# FishingReelController.net
KiCad netlist of a schematic drawn in EAGLE
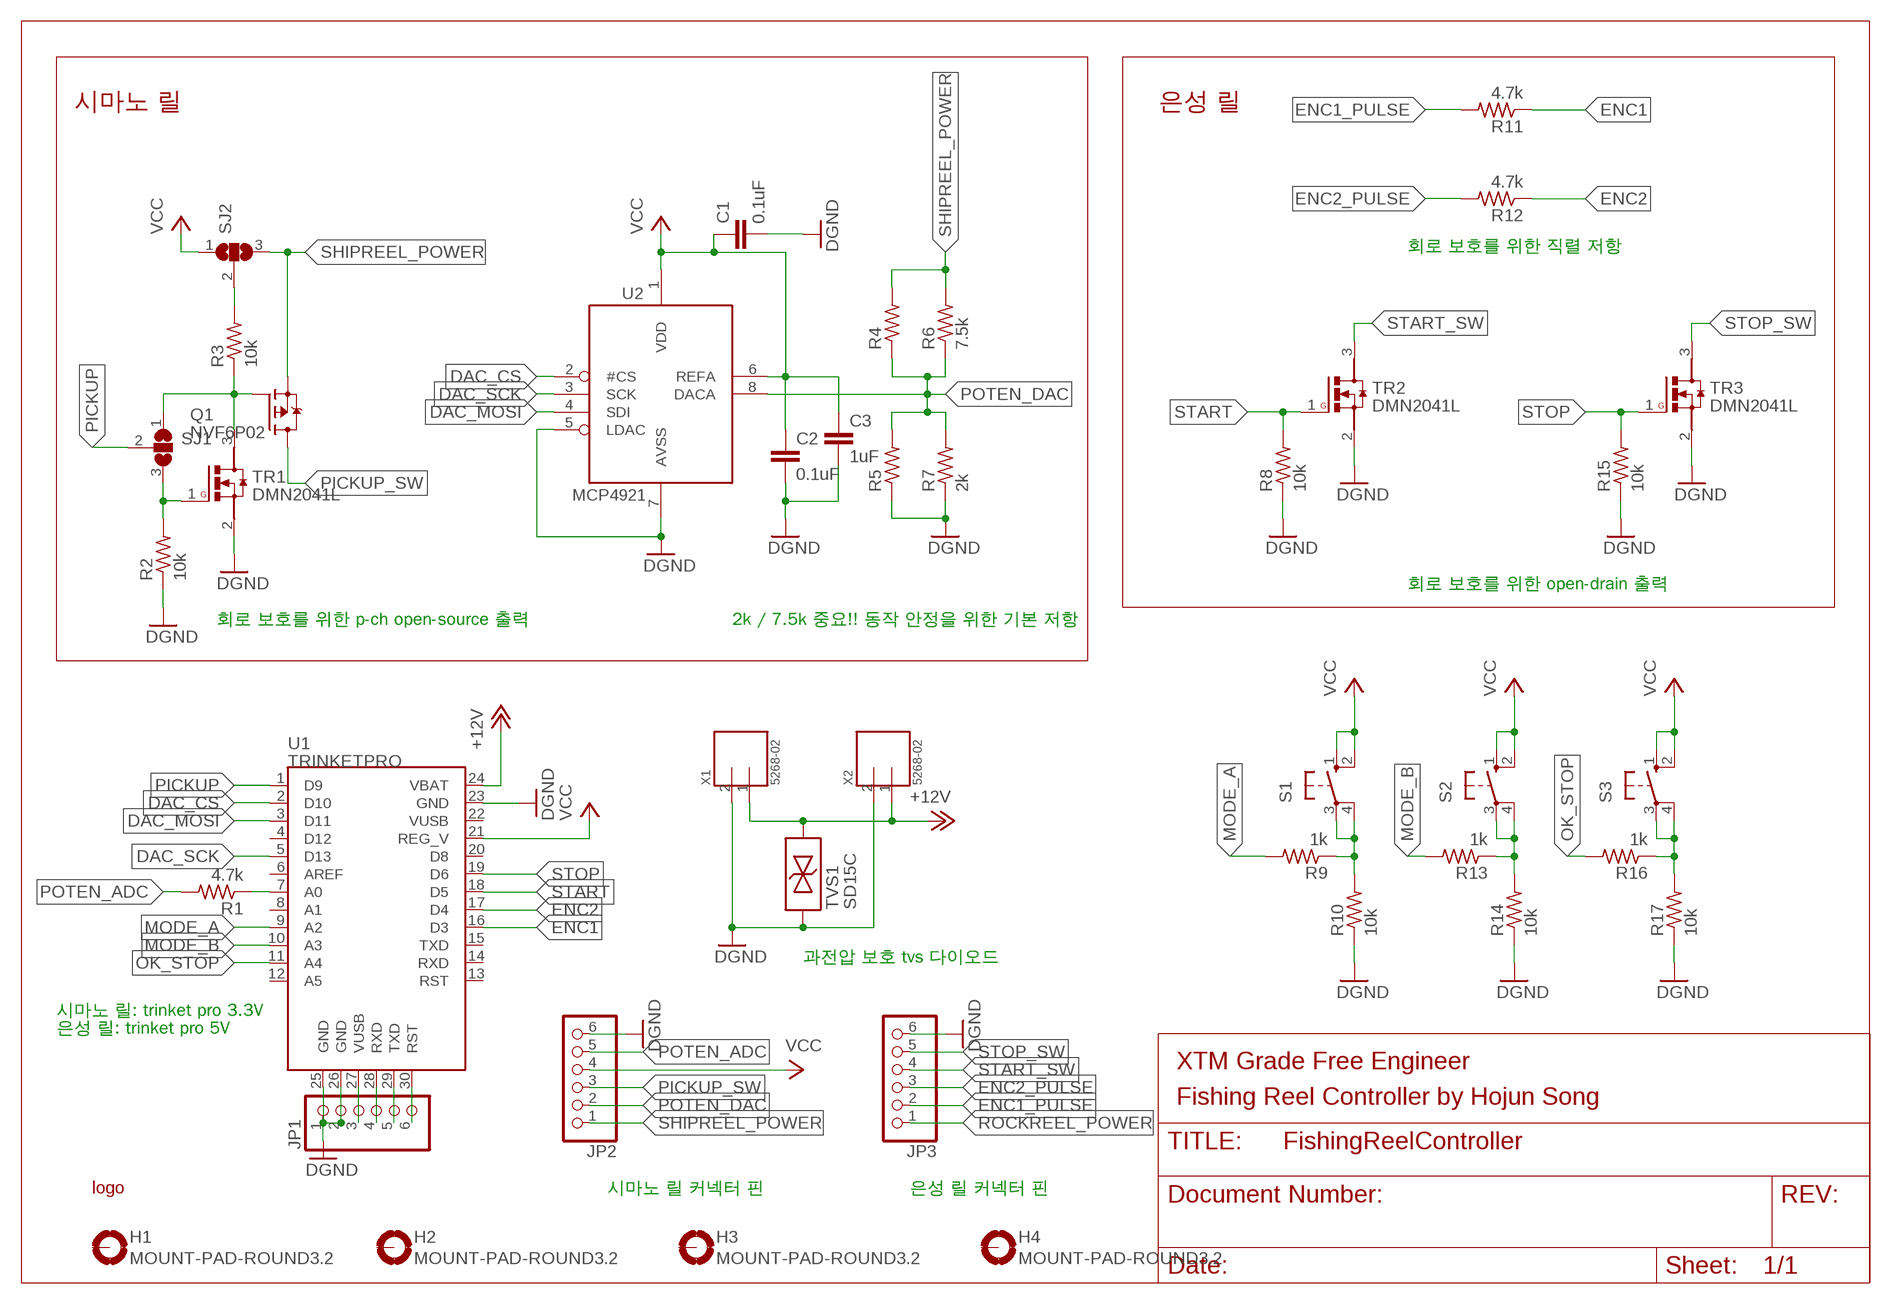
[diagram p0: schematic, sheet 1]

(export (version "E")
  (design (tool "Eeschema 10.0.6"))
  (components
    (comp (ref "C1")
      (value "0.1uF")
      (footprint "eagle-import:C0603(1608)")
      (libsource (lib "eagle-import") (part "C0603(1608)"))
    )
    (comp (ref "C2")
      (value "0.1uF")
      (footprint "eagle-import:C0603(1608)")
      (libsource (lib "eagle-import") (part "C0603(1608)"))
    )
    (comp (ref "C3")
      (value "1uF")
      (footprint "eagle-import:C0603(1608)")
      (libsource (lib "eagle-import") (part "C0603(1608)"))
    )
    (comp (ref "H1")
      (value "MOUNT-PAD-ROUND3.2")
      (footprint "eagle-import:3,2-PAD")
      (libsource (lib "eagle-import") (part "MOUNT-PAD-ROUND3.2"))
    )
    (comp (ref "H2")
      (value "MOUNT-PAD-ROUND3.2")
      (footprint "eagle-import:3,2-PAD")
      (libsource (lib "eagle-import") (part "MOUNT-PAD-ROUND3.2"))
    )
    (comp (ref "H3")
      (value "MOUNT-PAD-ROUND3.2")
      (footprint "eagle-import:3,2-PAD")
      (libsource (lib "eagle-import") (part "MOUNT-PAD-ROUND3.2"))
    )
    (comp (ref "H4")
      (value "MOUNT-PAD-ROUND3.2")
      (footprint "eagle-import:3,2-PAD")
      (libsource (lib "eagle-import") (part "MOUNT-PAD-ROUND3.2"))
    )
    (comp (ref "JP1")
      (value "PINHD-1X6CB")
      (footprint "eagle-import:1X06-CLEANBIG")
      (libsource (lib "eagle-import") (part "PINHD-1X6CB"))
    )
    (comp (ref "JP2")
      (value "PINHD-1X6CB")
      (footprint "eagle-import:1X06-CLEANBIG")
      (libsource (lib "eagle-import") (part "PINHD-1X6CB"))
    )
    (comp (ref "JP3")
      (value "PINHD-1X6CB")
      (footprint "eagle-import:1X06-CLEANBIG")
      (libsource (lib "eagle-import") (part "PINHD-1X6CB"))
    )
    (comp (ref "LOGO1")
      (value "GRADEFREELOGO-20")
      (footprint "eagle-import:GRADEFREELOGO-20")
      (libsource (lib "eagle-import") (part "GRADEFREELOGO-20"))
    )
    (comp (ref "Q1")
      (value "NVF6P02")
      (footprint "eagle-import:SOT223")
      (libsource (lib "eagle-import") (part "NVF6P02"))
    )
    (comp (ref "R1")
      (value "4.7k")
      (footprint "eagle-import:R0603(1608)")
      (libsource (lib "eagle-import") (part "R0603(1608)"))
    )
    (comp (ref "R2")
      (value "10k")
      (footprint "eagle-import:R0603(1608)")
      (libsource (lib "eagle-import") (part "R0603(1608)"))
    )
    (comp (ref "R3")
      (value "10k")
      (footprint "eagle-import:R0603(1608)")
      (libsource (lib "eagle-import") (part "R0603(1608)"))
    )
    (comp (ref "R4")
      (value "R0603(1608)")
      (footprint "eagle-import:R0603(1608)")
      (libsource (lib "eagle-import") (part "R0603(1608)"))
    )
    (comp (ref "R5")
      (value "R0603(1608)")
      (footprint "eagle-import:R0603(1608)")
      (libsource (lib "eagle-import") (part "R0603(1608)"))
    )
    (comp (ref "R6")
      (value "7.5k")
      (footprint "eagle-import:R0603(1608)")
      (libsource (lib "eagle-import") (part "R0603(1608)"))
    )
    (comp (ref "R7")
      (value "2k")
      (footprint "eagle-import:R0603(1608)")
      (libsource (lib "eagle-import") (part "R0603(1608)"))
    )
    (comp (ref "R8")
      (value "10k")
      (footprint "eagle-import:R0603(1608)")
      (libsource (lib "eagle-import") (part "R0603(1608)"))
    )
    (comp (ref "R9")
      (value "1k")
      (footprint "eagle-import:R0603(1608)")
      (libsource (lib "eagle-import") (part "R0603(1608)"))
    )
    (comp (ref "R10")
      (value "10k")
      (footprint "eagle-import:R0603(1608)")
      (libsource (lib "eagle-import") (part "R0603(1608)"))
    )
    (comp (ref "R11")
      (value "4.7k")
      (footprint "eagle-import:R0603(1608)")
      (libsource (lib "eagle-import") (part "R0603(1608)"))
    )
    (comp (ref "R12")
      (value "4.7k")
      (footprint "eagle-import:R0603(1608)")
      (libsource (lib "eagle-import") (part "R0603(1608)"))
    )
    (comp (ref "R13")
      (value "1k")
      (footprint "eagle-import:R0603(1608)")
      (libsource (lib "eagle-import") (part "R0603(1608)"))
    )
    (comp (ref "R14")
      (value "10k")
      (footprint "eagle-import:R0603(1608)")
      (libsource (lib "eagle-import") (part "R0603(1608)"))
    )
    (comp (ref "R15")
      (value "10k")
      (footprint "eagle-import:R0603(1608)")
      (libsource (lib "eagle-import") (part "R0603(1608)"))
    )
    (comp (ref "R16")
      (value "1k")
      (footprint "eagle-import:R0603(1608)")
      (libsource (lib "eagle-import") (part "R0603(1608)"))
    )
    (comp (ref "R17")
      (value "10k")
      (footprint "eagle-import:R0603(1608)")
      (libsource (lib "eagle-import") (part "R0603(1608)"))
    )
    (comp (ref "S1")
      (value "40-XX")
      (footprint "eagle-import:B3F-40XX")
      (fields (field (name "MF") "OMRON COMPONENTS USA") (field (name "MPN") "B3F-4000"))
      (libsource (lib "eagle-import") (part "40-XX"))
    )
    (comp (ref "S2")
      (value "40-XX")
      (footprint "eagle-import:B3F-40XX")
      (fields (field (name "MF") "OMRON COMPONENTS USA") (field (name "MPN") "B3F-4000"))
      (libsource (lib "eagle-import") (part "40-XX"))
    )
    (comp (ref "S3")
      (value "40-XX")
      (footprint "eagle-import:B3F-40XX")
      (fields (field (name "MF") "OMRON COMPONENTS USA") (field (name "MPN") "B3F-4000"))
      (libsource (lib "eagle-import") (part "40-XX"))
    )
    (comp (ref "SJ1")
      (value "SJ2W")
      (footprint "eagle-import:SJ_2")
      (libsource (lib "eagle-import") (part "SJ2W"))
    )
    (comp (ref "SJ2")
      (value "SJ2W")
      (footprint "eagle-import:SJ_2")
      (libsource (lib "eagle-import") (part "SJ2W"))
    )
    (comp (ref "TR1")
      (value "DMN2041L")
      (footprint "eagle-import:SOT23")
      (libsource (lib "eagle-import") (part "DMN2041L"))
    )
    (comp (ref "TR2")
      (value "DMN2041L")
      (footprint "eagle-import:SOT23")
      (libsource (lib "eagle-import") (part "DMN2041L"))
    )
    (comp (ref "TR3")
      (value "DMN2041L")
      (footprint "eagle-import:SOT23")
      (libsource (lib "eagle-import") (part "DMN2041L"))
    )
    (comp (ref "TVS1")
      (value "SD15C")
      (footprint "eagle-import:SOD-323-NOPOL")
      (libsource (lib "eagle-import") (part "SD0"))
    )
    (comp (ref "U1")
      (value "TRINKETPRO")
      (footprint "eagle-import:TRINKETPRO")
      (libsource (lib "eagle-import") (part "TRINKETPRO"))
    )
    (comp (ref "U2")
      (value "MCP4921")
      (footprint "eagle-import:DIL08")
      (libsource (lib "eagle-import") (part "MCP4921"))
    )
    (comp (ref "X1")
      (value "5268-02")
      (footprint "eagle-import:5628-02")
      (libsource (lib "eagle-import") (part "5268-02"))
    )
    (comp (ref "X2")
      (value "5268-02")
      (footprint "eagle-import:5628-02")
      (libsource (lib "eagle-import") (part "5268-02"))
    )
  )
  (nets
    (net (code "1") (name "+12V") (class "Default")
      (node (ref "TVS1") (pin "2") (pinfunction "P$2_2") (pintype "bidirectional"))
      (node (ref "U1") (pin "24") (pinfunction "VBAT_24") (pintype "bidirectional"))
      (node (ref "X1") (pin "1") (pinfunction "1_1") (pintype "bidirectional"))
      (node (ref "X2") (pin "1") (pinfunction "1_1") (pintype "bidirectional"))
    )
    (net (code "2") (name "DAC_CS") (class "Default")
      (node (ref "U1") (pin "2") (pinfunction "D10_2") (pintype "bidirectional"))
      (node (ref "U2") (pin "2") (pinfunction "#CS_2") (pintype "input"))
    )
    (net (code "3") (name "DAC_MOSI") (class "Default")
      (node (ref "U1") (pin "3") (pinfunction "D11_3") (pintype "bidirectional"))
      (node (ref "U2") (pin "4") (pinfunction "SDI_4") (pintype "input"))
    )
    (net (code "4") (name "DAC_SCK") (class "Default")
      (node (ref "U1") (pin "5") (pinfunction "D13_5") (pintype "bidirectional"))
      (node (ref "U2") (pin "3") (pinfunction "SCK_3") (pintype "input"))
    )
    (net (code "5") (name "DGND") (class "Default")
      (node (ref "C1") (pin "2") (pinfunction "2_2") (pintype "passive"))
      (node (ref "C2") (pin "2") (pinfunction "2_2") (pintype "passive"))
      (node (ref "C3") (pin "2") (pinfunction "2_2") (pintype "passive"))
      (node (ref "JP1") (pin "1") (pinfunction "1_1") (pintype "passive"))
      (node (ref "JP1") (pin "2") (pinfunction "2_2") (pintype "passive"))
      (node (ref "JP2") (pin "6") (pinfunction "6_6") (pintype "passive"))
      (node (ref "JP3") (pin "6") (pinfunction "6_6") (pintype "passive"))
      (node (ref "R10") (pin "1") (pinfunction "1_1") (pintype "passive"))
      (node (ref "R14") (pin "1") (pinfunction "1_1") (pintype "passive"))
      (node (ref "R15") (pin "1") (pinfunction "1_1") (pintype "passive"))
      (node (ref "R17") (pin "1") (pinfunction "1_1") (pintype "passive"))
      (node (ref "R2") (pin "1") (pinfunction "1_1") (pintype "passive"))
      (node (ref "R5") (pin "1") (pinfunction "1_1") (pintype "passive"))
      (node (ref "R7") (pin "1") (pinfunction "1_1") (pintype "passive"))
      (node (ref "R8") (pin "1") (pinfunction "1_1") (pintype "passive"))
      (node (ref "TR1") (pin "2") (pinfunction "S_2") (pintype "bidirectional"))
      (node (ref "TR2") (pin "2") (pinfunction "S_2") (pintype "bidirectional"))
      (node (ref "TR3") (pin "2") (pinfunction "S_2") (pintype "bidirectional"))
      (node (ref "TVS1") (pin "1") (pinfunction "P$1_1") (pintype "bidirectional"))
      (node (ref "U1") (pin "23") (pinfunction "GND_23") (pintype "bidirectional"))
      (node (ref "U1") (pin "25") (pinfunction "GND_25") (pintype "bidirectional"))
      (node (ref "U1") (pin "26") (pinfunction "GND_26") (pintype "bidirectional"))
      (node (ref "U2") (pin "5") (pinfunction "LDAC_5") (pintype "input"))
      (node (ref "U2") (pin "7") (pinfunction "AVSS_7") (pintype "power_in"))
      (node (ref "X1") (pin "2") (pinfunction "2_2") (pintype "bidirectional"))
      (node (ref "X2") (pin "2") (pinfunction "2_2") (pintype "bidirectional"))
    )
    (net (code "6") (name "ENC1") (class "Default")
      (node (ref "R11") (pin "1") (pinfunction "1_1") (pintype "passive"))
      (node (ref "U1") (pin "16") (pinfunction "D3_16") (pintype "bidirectional"))
    )
    (net (code "7") (name "ENC1_PULSE") (class "Default")
      (node (ref "JP3") (pin "2") (pinfunction "2_2") (pintype "passive"))
      (node (ref "R11") (pin "2") (pinfunction "2_2") (pintype "passive"))
    )
    (net (code "8") (name "ENC2") (class "Default")
      (node (ref "R12") (pin "1") (pinfunction "1_1") (pintype "passive"))
      (node (ref "U1") (pin "17") (pinfunction "D4_17") (pintype "bidirectional"))
    )
    (net (code "9") (name "ENC2_PULSE") (class "Default")
      (node (ref "JP3") (pin "3") (pinfunction "3_3") (pintype "passive"))
      (node (ref "R12") (pin "2") (pinfunction "2_2") (pintype "passive"))
    )
    (net (code "10") (name "MODE_A") (class "Default")
      (node (ref "R9") (pin "2") (pinfunction "2_2") (pintype "passive"))
      (node (ref "U1") (pin "9") (pinfunction "A2_9") (pintype "bidirectional"))
    )
    (net (code "11") (name "MODE_B") (class "Default")
      (node (ref "R13") (pin "2") (pinfunction "2_2") (pintype "passive"))
      (node (ref "U1") (pin "10") (pinfunction "A3_10") (pintype "bidirectional"))
    )
    (net (code "12") (name "Net-(JP1-Pad3)") (class "Default")
      (node (ref "JP1") (pin "3") (pinfunction "3_3") (pintype "passive"))
      (node (ref "U1") (pin "27") (pinfunction "VUSB_27") (pintype "bidirectional"))
    )
    (net (code "13") (name "Net-(JP1-Pad4)") (class "Default")
      (node (ref "JP1") (pin "4") (pinfunction "4_4") (pintype "passive"))
      (node (ref "U1") (pin "28") (pinfunction "RXD_28") (pintype "bidirectional"))
    )
    (net (code "14") (name "Net-(JP1-Pad5)") (class "Default")
      (node (ref "JP1") (pin "5") (pinfunction "5_5") (pintype "passive"))
      (node (ref "U1") (pin "29") (pinfunction "TXD_29") (pintype "bidirectional"))
    )
    (net (code "15") (name "Net-(JP1-Pad6)") (class "Default")
      (node (ref "JP1") (pin "6") (pinfunction "6_6") (pintype "passive"))
      (node (ref "U1") (pin "30") (pinfunction "RST_30") (pintype "bidirectional"))
    )
    (net (code "16") (name "Net-(Q1-G)") (class "Default")
      (node (ref "Q1") (pin "1") (pinfunction "G_1") (pintype "passive"))
      (node (ref "R3") (pin "1") (pinfunction "1_1") (pintype "passive"))
      (node (ref "SJ1") (pin "1") (pinfunction "1_1") (pintype "passive"))
      (node (ref "TR1") (pin "3") (pinfunction "D_3") (pintype "bidirectional"))
    )
    (net (code "17") (name "Net-(R3-Pad2)") (class "Default")
      (node (ref "R3") (pin "2") (pinfunction "2_2") (pintype "passive"))
      (node (ref "SJ2") (pin "2") (pinfunction "2_2") (pintype "passive"))
    )
    (net (code "18") (name "Net-(S1-P)") (class "Default")
      (node (ref "R10") (pin "2") (pinfunction "2_2") (pintype "passive"))
      (node (ref "R9") (pin "1") (pinfunction "1_1") (pintype "passive"))
      (node (ref "S1") (pin "3") (pinfunction "P_3") (pintype "passive"))
      (node (ref "S1") (pin "4") (pinfunction "P1_4") (pintype "passive"))
    )
    (net (code "19") (name "Net-(S2-P)") (class "Default")
      (node (ref "R13") (pin "1") (pinfunction "1_1") (pintype "passive"))
      (node (ref "R14") (pin "2") (pinfunction "2_2") (pintype "passive"))
      (node (ref "S2") (pin "3") (pinfunction "P_3") (pintype "passive"))
      (node (ref "S2") (pin "4") (pinfunction "P1_4") (pintype "passive"))
    )
    (net (code "20") (name "Net-(S3-P)") (class "Default")
      (node (ref "R16") (pin "1") (pinfunction "1_1") (pintype "passive"))
      (node (ref "R17") (pin "2") (pinfunction "2_2") (pintype "passive"))
      (node (ref "S3") (pin "3") (pinfunction "P_3") (pintype "passive"))
      (node (ref "S3") (pin "4") (pinfunction "P1_4") (pintype "passive"))
    )
    (net (code "21") (name "Net-(TR1-G)") (class "Default")
      (node (ref "R2") (pin "2") (pinfunction "2_2") (pintype "passive"))
      (node (ref "SJ1") (pin "3") (pinfunction "3_3") (pintype "passive"))
      (node (ref "TR1") (pin "1") (pinfunction "G_1") (pintype "bidirectional"))
    )
    (net (code "22") (name "Net-(U1-A0)") (class "Default")
      (node (ref "R1") (pin "1") (pinfunction "1_1") (pintype "passive"))
      (node (ref "U1") (pin "7") (pinfunction "A0_7") (pintype "bidirectional"))
    )
    (net (code "23") (name "OK_STOP") (class "Default")
      (node (ref "R16") (pin "2") (pinfunction "2_2") (pintype "passive"))
      (node (ref "U1") (pin "11") (pinfunction "A4_11") (pintype "bidirectional"))
    )
    (net (code "24") (name "PICKUP") (class "Default")
      (node (ref "SJ1") (pin "2") (pinfunction "2_2") (pintype "passive"))
      (node (ref "U1") (pin "1") (pinfunction "D9_1") (pintype "bidirectional"))
    )
    (net (code "25") (name "PICKUP_SW") (class "Default")
      (node (ref "JP2") (pin "3") (pinfunction "3_3") (pintype "passive"))
      (node (ref "Q1") (pin "2") (pinfunction "D_2") (pintype "passive"))
      (node (ref "Q1") (pin "4") (pinfunction "D_4") (pintype "passive"))
    )
    (net (code "26") (name "POTEN_ADC") (class "Default")
      (node (ref "JP2") (pin "5") (pinfunction "5_5") (pintype "passive"))
      (node (ref "R1") (pin "2") (pinfunction "2_2") (pintype "passive"))
    )
    (net (code "27") (name "POTEN_DAC") (class "Default")
      (node (ref "JP2") (pin "2") (pinfunction "2_2") (pintype "passive"))
      (node (ref "R4") (pin "1") (pinfunction "1_1") (pintype "passive"))
      (node (ref "R5") (pin "2") (pinfunction "2_2") (pintype "passive"))
      (node (ref "R6") (pin "1") (pinfunction "1_1") (pintype "passive"))
      (node (ref "R7") (pin "2") (pinfunction "2_2") (pintype "passive"))
      (node (ref "U2") (pin "8") (pinfunction "DACA_8") (pintype "output"))
    )
    (net (code "28") (name "ROCKREEL_POWER") (class "Default")
      (node (ref "JP3") (pin "1") (pinfunction "1_1") (pintype "passive"))
    )
    (net (code "29") (name "SHIPREEL_POWER") (class "Default")
      (node (ref "JP2") (pin "1") (pinfunction "1_1") (pintype "passive"))
      (node (ref "Q1") (pin "3") (pinfunction "S_3") (pintype "passive"))
      (node (ref "R4") (pin "2") (pinfunction "2_2") (pintype "passive"))
      (node (ref "R6") (pin "2") (pinfunction "2_2") (pintype "passive"))
      (node (ref "SJ2") (pin "3") (pinfunction "3_3") (pintype "passive"))
    )
    (net (code "30") (name "START") (class "Default")
      (node (ref "R8") (pin "2") (pinfunction "2_2") (pintype "passive"))
      (node (ref "TR2") (pin "1") (pinfunction "G_1") (pintype "bidirectional"))
      (node (ref "U1") (pin "18") (pinfunction "D5_18") (pintype "bidirectional"))
    )
    (net (code "31") (name "START_SW") (class "Default")
      (node (ref "JP3") (pin "4") (pinfunction "4_4") (pintype "passive"))
      (node (ref "TR2") (pin "3") (pinfunction "D_3") (pintype "bidirectional"))
    )
    (net (code "32") (name "STOP") (class "Default")
      (node (ref "R15") (pin "2") (pinfunction "2_2") (pintype "passive"))
      (node (ref "TR3") (pin "1") (pinfunction "G_1") (pintype "bidirectional"))
      (node (ref "U1") (pin "19") (pinfunction "D6_19") (pintype "bidirectional"))
    )
    (net (code "33") (name "STOP_SW") (class "Default")
      (node (ref "JP3") (pin "5") (pinfunction "5_5") (pintype "passive"))
      (node (ref "TR3") (pin "3") (pinfunction "D_3") (pintype "bidirectional"))
    )
    (net (code "34") (name "VCC") (class "Default")
      (node (ref "C1") (pin "1") (pinfunction "1_1") (pintype "passive"))
      (node (ref "C2") (pin "1") (pinfunction "1_1") (pintype "passive"))
      (node (ref "C3") (pin "1") (pinfunction "1_1") (pintype "passive"))
      (node (ref "JP2") (pin "4") (pinfunction "4_4") (pintype "passive"))
      (node (ref "S1") (pin "1") (pinfunction "S_1") (pintype "passive"))
      (node (ref "S1") (pin "2") (pinfunction "S1_2") (pintype "passive"))
      (node (ref "S2") (pin "1") (pinfunction "S_1") (pintype "passive"))
      (node (ref "S2") (pin "2") (pinfunction "S1_2") (pintype "passive"))
      (node (ref "S3") (pin "1") (pinfunction "S_1") (pintype "passive"))
      (node (ref "S3") (pin "2") (pinfunction "S1_2") (pintype "passive"))
      (node (ref "SJ2") (pin "1") (pinfunction "1_1") (pintype "passive"))
      (node (ref "U1") (pin "21") (pinfunction "REG_V_21") (pintype "bidirectional"))
      (node (ref "U2") (pin "1") (pinfunction "VDD_1") (pintype "power_in"))
      (node (ref "U2") (pin "6") (pinfunction "REFA_6") (pintype "input"))
    )
    (net (code "35") (name "unconnected-(H1-MOUNT-PadB3,2)") (class "Default")
      (node (ref "H1") (pin "B3,2") (pinfunction "MOUNT_B3,2") (pintype "passive"))
    )
    (net (code "36") (name "unconnected-(H2-MOUNT-PadB3,2)") (class "Default")
      (node (ref "H2") (pin "B3,2") (pinfunction "MOUNT_B3,2") (pintype "passive"))
    )
    (net (code "37") (name "unconnected-(H3-MOUNT-PadB3,2)") (class "Default")
      (node (ref "H3") (pin "B3,2") (pinfunction "MOUNT_B3,2") (pintype "passive"))
    )
    (net (code "38") (name "unconnected-(H4-MOUNT-PadB3,2)") (class "Default")
      (node (ref "H4") (pin "B3,2") (pinfunction "MOUNT_B3,2") (pintype "passive"))
    )
    (net (code "39") (name "unconnected-(U1-A1-Pad8)") (class "Default")
      (node (ref "U1") (pin "8") (pinfunction "A1_8") (pintype "bidirectional"))
    )
    (net (code "40") (name "unconnected-(U1-A5-Pad12)") (class "Default")
      (node (ref "U1") (pin "12") (pinfunction "A5_12") (pintype "bidirectional"))
    )
    (net (code "41") (name "unconnected-(U1-AREF-Pad6)") (class "Default")
      (node (ref "U1") (pin "6") (pinfunction "AREF_6") (pintype "bidirectional"))
    )
    (net (code "42") (name "unconnected-(U1-D8-Pad20)") (class "Default")
      (node (ref "U1") (pin "20") (pinfunction "D8_20") (pintype "bidirectional"))
    )
    (net (code "43") (name "unconnected-(U1-D12-Pad4)") (class "Default")
      (node (ref "U1") (pin "4") (pinfunction "D12_4") (pintype "bidirectional"))
    )
    (net (code "44") (name "unconnected-(U1-RST-Pad13)") (class "Default")
      (node (ref "U1") (pin "13") (pinfunction "RST_13") (pintype "bidirectional"))
    )
    (net (code "45") (name "unconnected-(U1-RXD-Pad14)") (class "Default")
      (node (ref "U1") (pin "14") (pinfunction "RXD_14") (pintype "bidirectional"))
    )
    (net (code "46") (name "unconnected-(U1-TXD-Pad15)") (class "Default")
      (node (ref "U1") (pin "15") (pinfunction "TXD_15") (pintype "bidirectional"))
    )
    (net (code "47") (name "unconnected-(U1-VUSB-Pad22)") (class "Default")
      (node (ref "U1") (pin "22") (pinfunction "VUSB_22") (pintype "bidirectional"))
    )
  )
)
